# STM32_microcontroller_power.net
KiCad netlist of a schematic drawn in Altium Designer
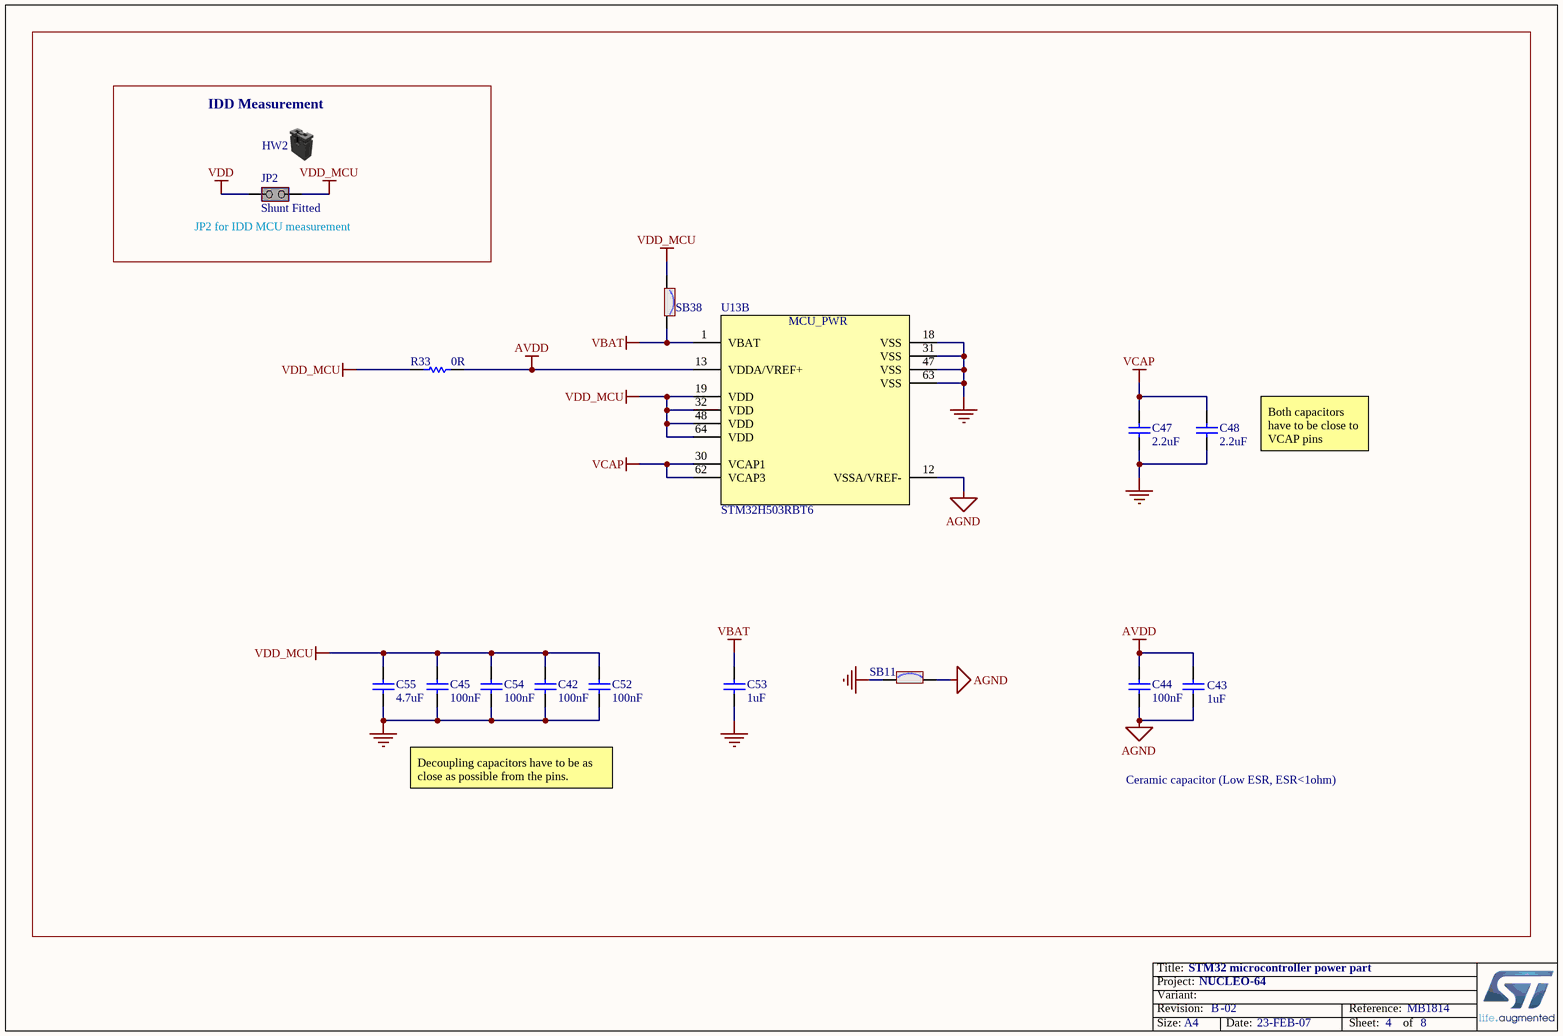
[diagram p0: STM32_microcontroller_power.SchDoc]

(export (version "E")
  (design (tool "Eeschema 10.0.6"))
  (components
    (comp (ref "C42")
      (value "100nF")
      (footprint "C0402")
      (description "Capacitor, MLCC, 100nF, 16V, X7R, 10%, 0402, T=0,5mm")
      (fields
        (field (name "INTERNAL_PART_NUMBER") "MCD-00102")
        (field (name "MANUFACTURER_PART_NUMBER") "CC0402KRX7R7BB104")
        (field (name "PROVIDED_BY") "Subcon")
      )
      (libsource (lib "MCD_PARTS_database") (part "Capacitor"))
    )
    (comp (ref "C43")
      (value "1uF")
      (footprint "C0603")
      (description "Capacitor, MLCC, 1uF, 16V, X5R, 10%, 0603, T=0,8mm")
      (fields
        (field (name "INTERNAL_PART_NUMBER") "MCD-00010")
        (field (name "MANUFACTURER_PART_NUMBER") "CC0603KRX5R7BB105")
        (field (name "PROVIDED_BY") "Subcon")
      )
      (libsource (lib "MCD_PARTS_database") (part "Capacitor"))
    )
    (comp (ref "C44")
      (value "100nF")
      (footprint "C0402")
      (description "Capacitor, MLCC, 100nF, 16V, X7R, 10%, 0402, T=0,5mm")
      (fields
        (field (name "INTERNAL_PART_NUMBER") "MCD-00102")
        (field (name "MANUFACTURER_PART_NUMBER") "CC0402KRX7R7BB104")
        (field (name "PROVIDED_BY") "Subcon")
      )
      (libsource (lib "MCD_PARTS_database") (part "Capacitor"))
    )
    (comp (ref "C45")
      (value "100nF")
      (footprint "C0402")
      (description "Capacitor, MLCC, 100nF, 16V, X7R, 10%, 0402, T=0,5mm")
      (fields
        (field (name "INTERNAL_PART_NUMBER") "MCD-00102")
        (field (name "MANUFACTURER_PART_NUMBER") "CC0402KRX7R7BB104")
        (field (name "PROVIDED_BY") "Subcon")
      )
      (libsource (lib "MCD_PARTS_database") (part "Capacitor"))
    )
    (comp (ref "C47")
      (value "2.2uF")
      (footprint "C0603")
      (description "Capacitor, MLCC, 2.2uF, 10V, X5R, +/- 10%, 0603, T=0,8mm")
      (fields (field (name "INTERNAL_PART_NUMBER") "MCD-00012") (field (name "BMS_PART_NUMBER") "9142010"))
      (libsource (lib "MCD_PARTS_database") (part "Capacitor"))
    )
    (comp (ref "C48")
      (value "2.2uF")
      (footprint "C0603")
      (description "Capacitor, MLCC, 2.2uF, 10V, X5R, +/- 10%, 0603, T=0,8mm")
      (fields (field (name "INTERNAL_PART_NUMBER") "MCD-00012") (field (name "BMS_PART_NUMBER") "9142010"))
      (libsource (lib "MCD_PARTS_database") (part "Capacitor"))
    )
    (comp (ref "C52")
      (value "100nF")
      (footprint "C0402")
      (description "Capacitor, MLCC, 100nF, 16V, X7R, 10%, 0402, T=0,5mm")
      (fields
        (field (name "INTERNAL_PART_NUMBER") "MCD-00102")
        (field (name "MANUFACTURER_PART_NUMBER") "CC0402KRX7R7BB104")
        (field (name "PROVIDED_BY") "Subcon")
      )
      (libsource (lib "MCD_PARTS_database") (part "Capacitor"))
    )
    (comp (ref "C53")
      (value "1uF")
      (footprint "C0603")
      (description "Capacitor, MLCC, 1uF, 16V, X5R, 10%, 0603, T=0,8mm")
      (fields
        (field (name "INTERNAL_PART_NUMBER") "MCD-00010")
        (field (name "MANUFACTURER_PART_NUMBER") "CC0603KRX5R7BB105")
        (field (name "PROVIDED_BY") "Subcon")
      )
      (libsource (lib "MCD_PARTS_database") (part "Capacitor"))
    )
    (comp (ref "C54")
      (value "100nF")
      (footprint "C0402")
      (description "Capacitor, MLCC, 100nF, 16V, X7R, 10%, 0402, T=0,5mm")
      (fields
        (field (name "INTERNAL_PART_NUMBER") "MCD-00102")
        (field (name "MANUFACTURER_PART_NUMBER") "CC0402KRX7R7BB104")
        (field (name "PROVIDED_BY") "Subcon")
      )
      (libsource (lib "MCD_PARTS_database") (part "Capacitor"))
    )
    (comp (ref "C55")
      (value "4.7uF")
      (footprint "C0603")
      (description "Capacitor, MLCC, 4.7uF, 16V, X5R, 10%, 0603, T=0.8mm")
      (fields
        (field (name "INTERNAL_PART_NUMBER") "MCD-00009")
        (field (name "MANUFACTURER_PART_NUMBER") "CC0603KRX5R7BB475")
        (field (name "PROVIDED_BY") "subcon")
      )
      (libsource (lib "MCD_PARTS_database") (part "Capacitor"))
    )
    (comp (ref "HW2")
      (value "~")
      (description "SHUNT 2.54mm BLACK")
      (fields
        (field (name "INTERNAL_PART_NUMBER") "MCD-00043")
        (field (name "MANUFACTURER_PART_NUMBER") "SNT-100-BK-G")
        (field (name "PROVIDED_BY") "Subcon")
      )
      (libsource (lib "MCD_PARTS_database") (part "Shunt Black 2.54mm"))
    )
    (comp (ref "JP2")
      (value "Shunt Fitted")
      (footprint "CON_SAMTEC_TSW-102-07-G-S")
      (description "Header, 2x1, 2,54mm, VR, TH, Height 5.84mm/2.54mm - Shunt Fitted by default")
      (fields
        (field (name "INTERNAL_PART_NUMBER") "MCD-00683")
        (field (name "MANUFACTURER_PART_NUMBER") "TSW-102-07-x-S")
        (field (name "PROVIDED_BY") "Subcon")
      )
      (libsource (lib "MCD_PARTS_database") (part "Jumper_Header 2x1 Fitted"))
    )
    (comp (ref "R33")
      (value "0R")
      (footprint "R0603")
      (description "Resistor, 0R, 0603, +/-5%, 1/10W")
      (fields (field (name "INTERNAL_PART_NUMBER") "MCD-00056") (field (name "MANUFACTURER") "YAGEO"))
      (libsource (lib "MCD_PARTS_database") (part "Resistor"))
    )
    (comp (ref "SB11")
      (value "~")
      (footprint "SOLDER-BRIDGE_R0603-0R")
      (description "Solder Bridge ON")
      (fields
        (field (name "INTERNAL_PART_NUMBER") "MCD-00071")
        (field (name "MANUFACTURER_PART_NUMBER") "RC0603JR-070RL")
        (field (name "PROVIDED_BY") "SUBCO")
      )
      (libsource (lib "MCD_PARTS_database") (part "SB_ON"))
    )
    (comp (ref "SB38")
      (value "~")
      (footprint "SOLDER-BRIDGE_R0603-0R")
      (description "Solder Bridge ON")
      (fields
        (field (name "INTERNAL_PART_NUMBER") "MCD-00071")
        (field (name "MANUFACTURER_PART_NUMBER") "RC0603JR-070RL")
        (field (name "PROVIDED_BY") "SUBCO")
      )
      (libsource (lib "") (part "SB_ON_1"))
    )
    (comp (ref "U13")
      (value "STM32H503RBT6")
      (footprint "ICC_LQFP64_10X10_P050_SOCKET_YAMAICHI_IC149-064-069-B5_NM")
      (description "MCU, Arm Cortex-M33, 250MHz, 32-bit MCU, 128KB flash, 32KB SRAM")
      (fields
        (field (name "INTERNAL_PART_NUMBER") "MCD-02438")
        (field (name "MANUFACTURER") "STMICROELECTRONICS")
      )
      (libsource (lib "MCD_PARTS_database") (part "STM32H503RBH6"))
    )
  )
  (nets
    (net (code "1") (name "AGND") (class "Default")
      (node (ref "C43") (pin "1") (pinfunction "1_1") (pintype "passive"))
      (node (ref "C44") (pin "1") (pinfunction "1_1") (pintype "passive"))
      (node (ref "SB11") (pin "2") (pinfunction "2_2") (pintype "passive"))
      (node (ref "U13") (pin "12") (pinfunction "VSSA/VREF-_12") (pintype "passive"))
    )
    (net (code "2") (name "AVDD") (class "Default")
      (node (ref "C43") (pin "2") (pinfunction "2_2") (pintype "passive"))
      (node (ref "C44") (pin "2") (pinfunction "2_2") (pintype "passive"))
      (node (ref "R33") (pin "2") (pinfunction "2_2") (pintype "passive"))
      (node (ref "U13") (pin "13") (pinfunction "VDDA/VREF+_13") (pintype "passive"))
    )
    (net (code "3") (name "GND") (class "Default")
      (node (ref "C42") (pin "1") (pinfunction "1_1") (pintype "passive"))
      (node (ref "C45") (pin "1") (pinfunction "1_1") (pintype "passive"))
      (node (ref "C47") (pin "1") (pinfunction "1_1") (pintype "passive"))
      (node (ref "C48") (pin "1") (pinfunction "1_1") (pintype "passive"))
      (node (ref "C52") (pin "1") (pinfunction "1_1") (pintype "passive"))
      (node (ref "C53") (pin "1") (pinfunction "1_1") (pintype "passive"))
      (node (ref "C54") (pin "1") (pinfunction "1_1") (pintype "passive"))
      (node (ref "C55") (pin "1") (pinfunction "1_1") (pintype "passive"))
      (node (ref "SB11") (pin "1") (pinfunction "1_1") (pintype "passive"))
      (node (ref "U13") (pin "18") (pinfunction "VSS_18") (pintype "passive"))
      (node (ref "U13") (pin "31") (pinfunction "VSS_31") (pintype "passive"))
      (node (ref "U13") (pin "47") (pinfunction "VSS_47") (pintype "passive"))
      (node (ref "U13") (pin "63") (pinfunction "VSS_63") (pintype "passive"))
    )
    (net (code "4") (name "VBAT") (class "Default")
      (node (ref "C53") (pin "2") (pinfunction "2_2") (pintype "passive"))
      (node (ref "SB38") (pin "2") (pinfunction "2_2") (pintype "passive"))
      (node (ref "U13") (pin "1") (pinfunction "VBAT_1") (pintype "passive"))
    )
    (net (code "5") (name "VCAP") (class "Default")
      (node (ref "C47") (pin "2") (pinfunction "2_2") (pintype "passive"))
      (node (ref "C48") (pin "2") (pinfunction "2_2") (pintype "passive"))
      (node (ref "U13") (pin "30") (pinfunction "VCAP1_30") (pintype "passive"))
      (node (ref "U13") (pin "62") (pinfunction "VCAP3_62") (pintype "passive"))
    )
    (net (code "6") (name "VDD") (class "Default")
      (node (ref "JP2") (pin "1") (pinfunction "COMMON_1") (pintype "passive"))
    )
    (net (code "7") (name "VDD_MCU") (class "Default")
      (node (ref "C42") (pin "2") (pinfunction "2_2") (pintype "passive"))
      (node (ref "C45") (pin "2") (pinfunction "2_2") (pintype "passive"))
      (node (ref "C52") (pin "2") (pinfunction "2_2") (pintype "passive"))
      (node (ref "C54") (pin "2") (pinfunction "2_2") (pintype "passive"))
      (node (ref "C55") (pin "2") (pinfunction "2_2") (pintype "passive"))
      (node (ref "JP2") (pin "2") (pinfunction "NO_2") (pintype "passive"))
      (node (ref "R33") (pin "1") (pinfunction "1_1") (pintype "passive"))
      (node (ref "SB38") (pin "1") (pinfunction "1_1") (pintype "passive"))
      (node (ref "U13") (pin "19") (pinfunction "VDD_19") (pintype "passive"))
      (node (ref "U13") (pin "32") (pinfunction "VDD_32") (pintype "passive"))
      (node (ref "U13") (pin "48") (pinfunction "VDD_48") (pintype "passive"))
      (node (ref "U13") (pin "64") (pinfunction "VDD_64") (pintype "passive"))
    )
  )
)
